# Slaves-Power-board.net
KiCad netlist of a schematic drawn in EAGLE
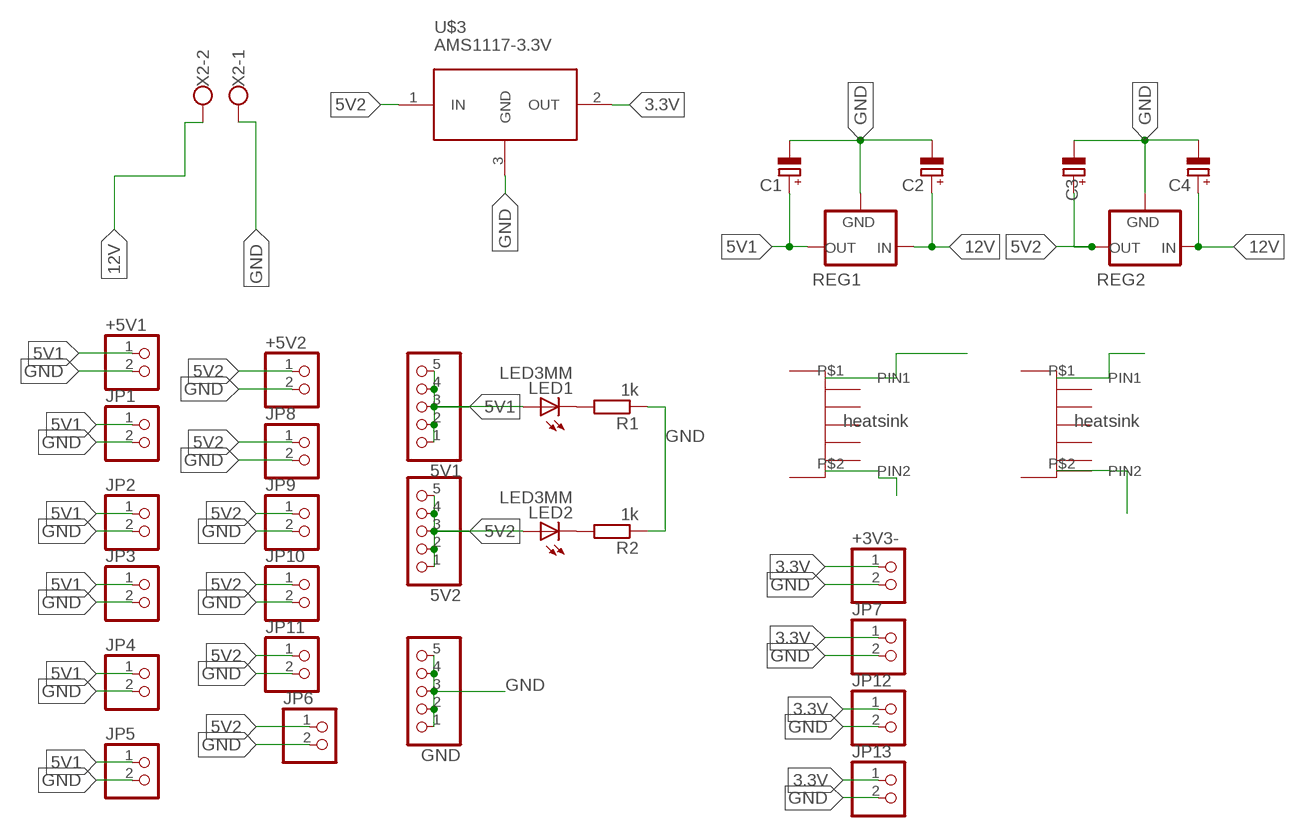
[diagram p0: schematic, sheet 1]

(export (version "E")
  (design (tool "Eeschema 10.0.6"))
  (components
    (comp (ref "+3V3-")
      (value "PINHD-2_DATA")
      (footprint "eagle-import:1X02_DATA")
      (libsource (lib "eagle-import") (part "PINHD-2_DATA"))
    )
    (comp (ref "+5V1")
      (value "PINHD-2_DATA")
      (footprint "eagle-import:1X02_DATA")
      (libsource (lib "eagle-import") (part "PINHD-2_DATA"))
    )
    (comp (ref "+5V2")
      (value "PINHD-2_DATA")
      (footprint "eagle-import:1X02_DATA")
      (libsource (lib "eagle-import") (part "PINHD-2_DATA"))
    )
    (comp (ref "5V1")
      (value "PINHD-1X5")
      (footprint "eagle-import:1X05")
      (libsource (lib "eagle-import") (part "PINHD-1X5"))
    )
    (comp (ref "5V2")
      (value "PINHD-1X5")
      (footprint "eagle-import:1X05")
      (libsource (lib "eagle-import") (part "PINHD-1X5"))
    )
    (comp (ref "C1")
      (value "CAP_POL")
      (footprint "eagle-import:E3,5-8")
      (libsource (lib "eagle-import") (part "CAP_POL"))
    )
    (comp (ref "C2")
      (value "CAP_POL")
      (footprint "eagle-import:E3,5-8")
      (libsource (lib "eagle-import") (part "CAP_POL"))
    )
    (comp (ref "C3")
      (value "CAP_POL")
      (footprint "eagle-import:E3,5-8")
      (libsource (lib "eagle-import") (part "CAP_POL"))
    )
    (comp (ref "C4")
      (value "CAP_POL")
      (footprint "eagle-import:E3,5-8")
      (libsource (lib "eagle-import") (part "CAP_POL"))
    )
    (comp (ref "GND")
      (value "PINHD-1X5")
      (footprint "eagle-import:1X05")
      (libsource (lib "eagle-import") (part "PINHD-1X5"))
    )
    (comp (ref "JP1")
      (value "PINHD-2_DATA")
      (footprint "eagle-import:1X02_DATA")
      (libsource (lib "eagle-import") (part "PINHD-2_DATA"))
    )
    (comp (ref "JP2")
      (value "PINHD-2_DATA")
      (footprint "eagle-import:1X02_DATA")
      (libsource (lib "eagle-import") (part "PINHD-2_DATA"))
    )
    (comp (ref "JP3")
      (value "PINHD-2_DATA")
      (footprint "eagle-import:1X02_DATA")
      (libsource (lib "eagle-import") (part "PINHD-2_DATA"))
    )
    (comp (ref "JP4")
      (value "PINHD-2_DATA")
      (footprint "eagle-import:1X02_DATA")
      (libsource (lib "eagle-import") (part "PINHD-2_DATA"))
    )
    (comp (ref "JP5")
      (value "PINHD-2_DATA")
      (footprint "eagle-import:1X02_DATA")
      (libsource (lib "eagle-import") (part "PINHD-2_DATA"))
    )
    (comp (ref "JP6")
      (value "PINHD-2_DATA")
      (footprint "eagle-import:1X02_DATA")
      (libsource (lib "eagle-import") (part "PINHD-2_DATA"))
    )
    (comp (ref "JP7")
      (value "PINHD-2_DATA")
      (footprint "eagle-import:1X02_DATA")
      (libsource (lib "eagle-import") (part "PINHD-2_DATA"))
    )
    (comp (ref "JP8")
      (value "PINHD-2_DATA")
      (footprint "eagle-import:1X02_DATA")
      (libsource (lib "eagle-import") (part "PINHD-2_DATA"))
    )
    (comp (ref "JP9")
      (value "PINHD-2_DATA")
      (footprint "eagle-import:1X02_DATA")
      (libsource (lib "eagle-import") (part "PINHD-2_DATA"))
    )
    (comp (ref "JP10")
      (value "PINHD-2_DATA")
      (footprint "eagle-import:1X02_DATA")
      (libsource (lib "eagle-import") (part "PINHD-2_DATA"))
    )
    (comp (ref "JP11")
      (value "PINHD-2_DATA")
      (footprint "eagle-import:1X02_DATA")
      (libsource (lib "eagle-import") (part "PINHD-2_DATA"))
    )
    (comp (ref "JP12")
      (value "PINHD-2_DATA")
      (footprint "eagle-import:1X02_DATA")
      (libsource (lib "eagle-import") (part "PINHD-2_DATA"))
    )
    (comp (ref "JP13")
      (value "PINHD-2_DATA")
      (footprint "eagle-import:1X02_DATA")
      (libsource (lib "eagle-import") (part "PINHD-2_DATA"))
    )
    (comp (ref "LED1")
      (value "LED3MM")
      (footprint "eagle-import:LED3MM")
      (libsource (lib "eagle-import") (part "LED3MM"))
    )
    (comp (ref "LED2")
      (value "LED3MM")
      (footprint "eagle-import:LED3MM")
      (libsource (lib "eagle-import") (part "LED3MM"))
    )
    (comp (ref "R1")
      (value "1k")
      (footprint "eagle-import:0204_7")
      (libsource (lib "eagle-import") (part "R-EU_0204/7"))
    )
    (comp (ref "R2")
      (value "1k")
      (footprint "eagle-import:0204_7")
      (libsource (lib "eagle-import") (part "R-EU_0204/7"))
    )
    (comp (ref "REG1")
      (value "78XXS")
      (footprint "eagle-import:78XXS")
      (libsource (lib "eagle-import") (part "78XXS"))
    )
    (comp (ref "REG2")
      (value "78XXS")
      (footprint "eagle-import:78XXS")
      (libsource (lib "eagle-import") (part "78XXS"))
    )
    (comp (ref "U$1")
      (value "HEAT-SINK")
      (footprint "eagle-import:HEAT_SINK")
      (libsource (lib "eagle-import") (part "HEAT-SINK"))
    )
    (comp (ref "U$2")
      (value "HEAT-SINK")
      (footprint "eagle-import:HEAT_SINK")
      (libsource (lib "eagle-import") (part "HEAT-SINK"))
    )
    (comp (ref "U$3")
      (value "AMS1117-3.3V")
      (footprint "eagle-import:REG-AMS1117-3P#V")
      (libsource (lib "eagle-import") (part "REG-AMS1117-3P-#V5.0V"))
    )
    (comp (ref "X2")
      (value "ROSTA.POWER")
      (footprint "eagle-import:W239-302")
      (libsource (lib "eagle-import") (part "ROSTA.POWER"))
    )
  )
  (nets
    (net (code "1") (name "3.3V") (class "Default")
      (node (ref "+3V3-") (pin "1") (pinfunction "1_1") (pintype "passive"))
      (node (ref "JP12") (pin "1") (pinfunction "1_1") (pintype "passive"))
      (node (ref "JP13") (pin "1") (pinfunction "1_1") (pintype "passive"))
      (node (ref "JP7") (pin "1") (pinfunction "1_1") (pintype "passive"))
      (node (ref "U$3") (pin "2") (pinfunction "OUT_2") (pintype "bidirectional"))
    )
    (net (code "2") (name "5V1") (class "Default")
      (node (ref "+5V1") (pin "1") (pinfunction "1_1") (pintype "passive"))
      (node (ref "5V1") (pin "1") (pinfunction "1_1") (pintype "passive"))
      (node (ref "5V1") (pin "2") (pinfunction "2_2") (pintype "passive"))
      (node (ref "5V1") (pin "3") (pinfunction "3_3") (pintype "passive"))
      (node (ref "5V1") (pin "4") (pinfunction "4_4") (pintype "passive"))
      (node (ref "5V1") (pin "5") (pinfunction "5_5") (pintype "passive"))
      (node (ref "C1") (pin "+") (pinfunction "+_+") (pintype "passive"))
      (node (ref "JP1") (pin "1") (pinfunction "1_1") (pintype "passive"))
      (node (ref "JP2") (pin "1") (pinfunction "1_1") (pintype "passive"))
      (node (ref "JP3") (pin "1") (pinfunction "1_1") (pintype "passive"))
      (node (ref "JP4") (pin "1") (pinfunction "1_1") (pintype "passive"))
      (node (ref "JP5") (pin "1") (pinfunction "1_1") (pintype "passive"))
      (node (ref "LED1") (pin "A") (pinfunction "A_A") (pintype "passive"))
      (node (ref "REG1") (pin "OUT") (pinfunction "OUT_OUT") (pintype "passive"))
    )
    (net (code "3") (name "5V2") (class "Default")
      (node (ref "+5V2") (pin "1") (pinfunction "1_1") (pintype "passive"))
      (node (ref "5V2") (pin "1") (pinfunction "1_1") (pintype "passive"))
      (node (ref "5V2") (pin "2") (pinfunction "2_2") (pintype "passive"))
      (node (ref "5V2") (pin "3") (pinfunction "3_3") (pintype "passive"))
      (node (ref "5V2") (pin "4") (pinfunction "4_4") (pintype "passive"))
      (node (ref "5V2") (pin "5") (pinfunction "5_5") (pintype "passive"))
      (node (ref "C3") (pin "+") (pinfunction "+_+") (pintype "passive"))
      (node (ref "JP10") (pin "1") (pinfunction "1_1") (pintype "passive"))
      (node (ref "JP11") (pin "1") (pinfunction "1_1") (pintype "passive"))
      (node (ref "JP6") (pin "1") (pinfunction "1_1") (pintype "passive"))
      (node (ref "JP8") (pin "1") (pinfunction "1_1") (pintype "passive"))
      (node (ref "JP9") (pin "1") (pinfunction "1_1") (pintype "passive"))
      (node (ref "LED2") (pin "A") (pinfunction "A_A") (pintype "passive"))
      (node (ref "REG2") (pin "OUT") (pinfunction "OUT_OUT") (pintype "passive"))
      (node (ref "U$3") (pin "1") (pinfunction "IN_1") (pintype "bidirectional"))
    )
    (net (code "4") (name "12V") (class "Default")
      (node (ref "C2") (pin "+") (pinfunction "+_+") (pintype "passive"))
      (node (ref "C4") (pin "+") (pinfunction "+_+") (pintype "passive"))
      (node (ref "REG1") (pin "IN") (pinfunction "IN_IN") (pintype "input"))
      (node (ref "REG2") (pin "IN") (pinfunction "IN_IN") (pintype "input"))
      (node (ref "X2") (pin "2") (pinfunction "KL_2") (pintype "passive"))
    )
    (net (code "5") (name "GND") (class "Default")
      (node (ref "+3V3-") (pin "2") (pinfunction "2_2") (pintype "passive"))
      (node (ref "+5V1") (pin "2") (pinfunction "2_2") (pintype "passive"))
      (node (ref "+5V2") (pin "2") (pinfunction "2_2") (pintype "passive"))
      (node (ref "C1") (pin "-") (pinfunction "-_-") (pintype "passive"))
      (node (ref "C2") (pin "-") (pinfunction "-_-") (pintype "passive"))
      (node (ref "C3") (pin "-") (pinfunction "-_-") (pintype "passive"))
      (node (ref "C4") (pin "-") (pinfunction "-_-") (pintype "passive"))
      (node (ref "GND") (pin "1") (pinfunction "1_1") (pintype "passive"))
      (node (ref "GND") (pin "2") (pinfunction "2_2") (pintype "passive"))
      (node (ref "GND") (pin "3") (pinfunction "3_3") (pintype "passive"))
      (node (ref "GND") (pin "4") (pinfunction "4_4") (pintype "passive"))
      (node (ref "GND") (pin "5") (pinfunction "5_5") (pintype "passive"))
      (node (ref "JP1") (pin "2") (pinfunction "2_2") (pintype "passive"))
      (node (ref "JP10") (pin "2") (pinfunction "2_2") (pintype "passive"))
      (node (ref "JP11") (pin "2") (pinfunction "2_2") (pintype "passive"))
      (node (ref "JP12") (pin "2") (pinfunction "2_2") (pintype "passive"))
      (node (ref "JP13") (pin "2") (pinfunction "2_2") (pintype "passive"))
      (node (ref "JP2") (pin "2") (pinfunction "2_2") (pintype "passive"))
      (node (ref "JP3") (pin "2") (pinfunction "2_2") (pintype "passive"))
      (node (ref "JP4") (pin "2") (pinfunction "2_2") (pintype "passive"))
      (node (ref "JP5") (pin "2") (pinfunction "2_2") (pintype "passive"))
      (node (ref "JP6") (pin "2") (pinfunction "2_2") (pintype "passive"))
      (node (ref "JP7") (pin "2") (pinfunction "2_2") (pintype "passive"))
      (node (ref "JP8") (pin "2") (pinfunction "2_2") (pintype "passive"))
      (node (ref "JP9") (pin "2") (pinfunction "2_2") (pintype "passive"))
      (node (ref "R1") (pin "1") (pinfunction "1_1") (pintype "passive"))
      (node (ref "R2") (pin "1") (pinfunction "1_1") (pintype "passive"))
      (node (ref "REG1") (pin "GND") (pinfunction "GND_GND") (pintype "input"))
      (node (ref "REG2") (pin "GND") (pinfunction "GND_GND") (pintype "input"))
      (node (ref "U$3") (pin "3") (pinfunction "GND_3") (pintype "bidirectional"))
      (node (ref "X2") (pin "1") (pinfunction "KL_1") (pintype "passive"))
    )
    (net (code "6") (name "Net-(LED1-C)") (class "Default")
      (node (ref "LED1") (pin "K") (pinfunction "C_K") (pintype "passive"))
      (node (ref "R1") (pin "2") (pinfunction "2_2") (pintype "passive"))
    )
    (net (code "7") (name "Net-(LED2-C)") (class "Default")
      (node (ref "LED2") (pin "K") (pinfunction "C_K") (pintype "passive"))
      (node (ref "R2") (pin "2") (pinfunction "2_2") (pintype "passive"))
    )
    (net (code "8") (name "unconnected-(U$1-PIN1-PadP$1)") (class "Default")
      (node (ref "U$1") (pin "P$1") (pinfunction "PIN1_P$1") (pintype "bidirectional"))
    )
    (net (code "9") (name "unconnected-(U$1-PIN2-PadP$2)") (class "Default")
      (node (ref "U$1") (pin "P$2") (pinfunction "PIN2_P$2") (pintype "bidirectional"))
    )
    (net (code "10") (name "unconnected-(U$2-PIN1-PadP$1)") (class "Default")
      (node (ref "U$2") (pin "P$1") (pinfunction "PIN1_P$1") (pintype "bidirectional"))
    )
    (net (code "11") (name "unconnected-(U$2-PIN2-PadP$2)") (class "Default")
      (node (ref "U$2") (pin "P$2") (pinfunction "PIN2_P$2") (pintype "bidirectional"))
    )
  )
)
